# midi-switcher-smt.net
KiCad netlist of a schematic drawn in EAGLE
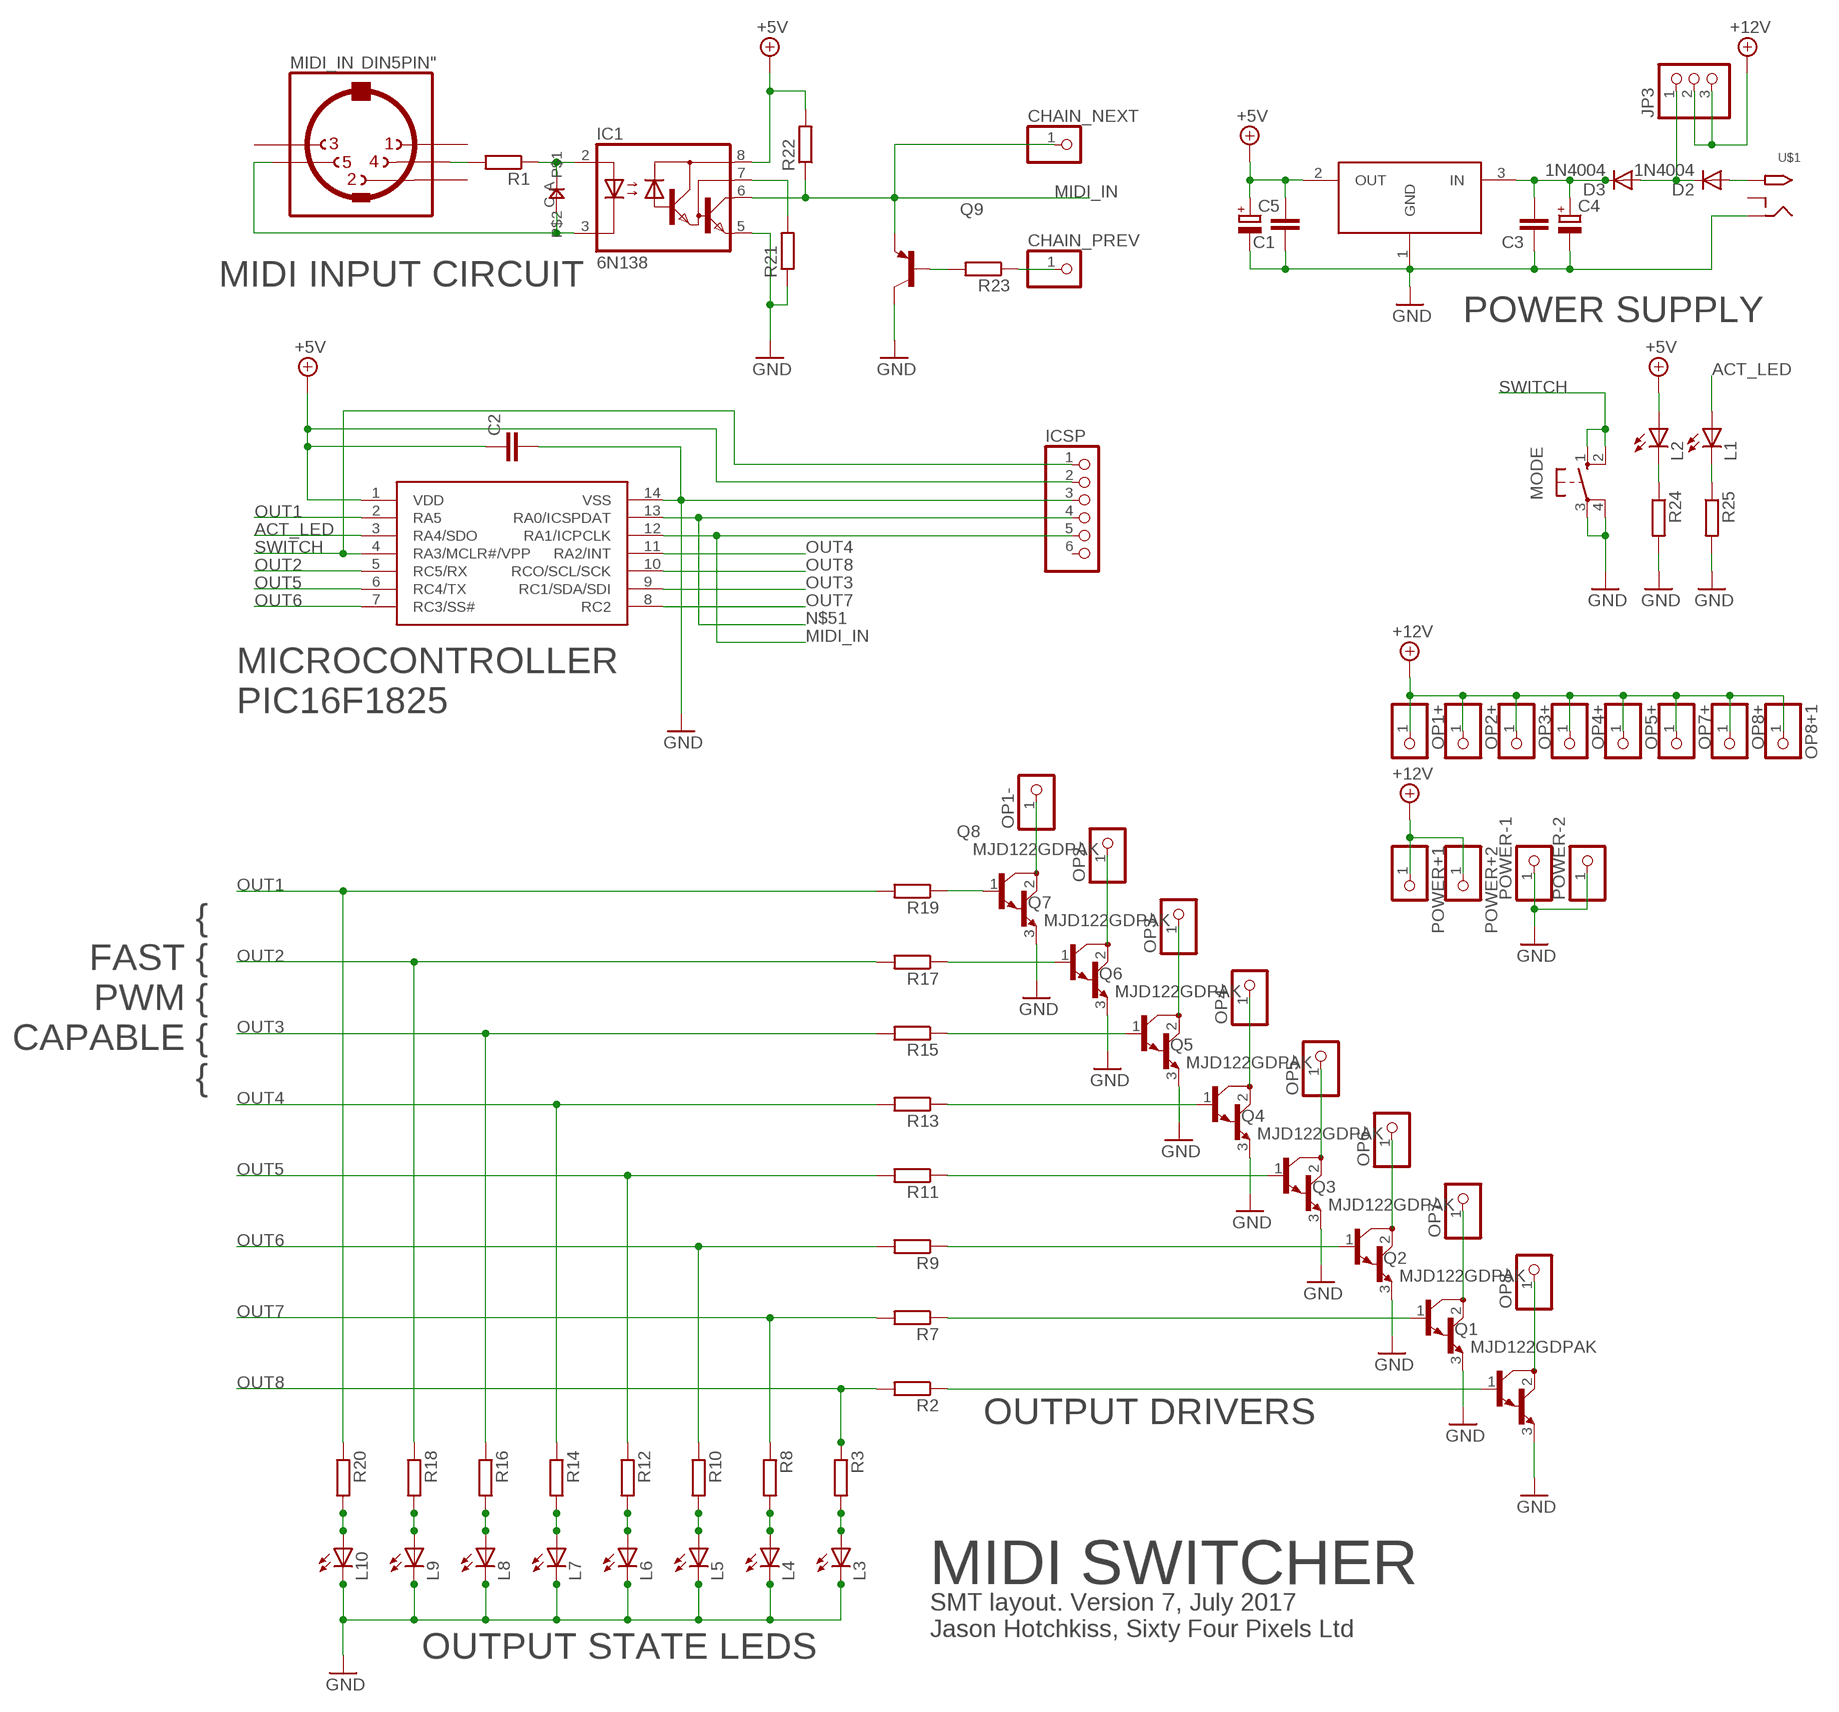
[diagram p0: schematic, sheet 1]

(export (version "E")
  (design (tool "Eeschema 10.0.6"))
  (components
    (comp (ref "C1")
      (value "C-EUC0805")
      (footprint "eagle-import:C0805")
      (libsource (lib "eagle-import") (part "C-EUC0805"))
    )
    (comp (ref "C2")
      (value "C-EUC0805")
      (footprint "eagle-import:C0805")
      (libsource (lib "eagle-import") (part "C-EUC0805"))
    )
    (comp (ref "C3")
      (value "C-EUC0805")
      (footprint "eagle-import:C0805")
      (libsource (lib "eagle-import") (part "C-EUC0805"))
    )
    (comp (ref "C4")
      (value "CPOL-EUE2.5-7")
      (footprint "eagle-import:E2,5-7")
      (libsource (lib "eagle-import") (part "CPOL-EUE2.5-7"))
    )
    (comp (ref "C5")
      (value "CPOL-EUE2.5-6")
      (footprint "eagle-import:E2,5-6")
      (libsource (lib "eagle-import") (part "CPOL-EUE2.5-6"))
    )
    (comp (ref "CHAIN_NEXT")
      (value "PINHD-1X1")
      (footprint "eagle-import:1X01")
      (libsource (lib "eagle-import") (part "PINHD-1X1"))
    )
    (comp (ref "CHAIN_PREV")
      (value "PINHD-1X1")
      (footprint "eagle-import:1X01")
      (libsource (lib "eagle-import") (part "PINHD-1X1"))
    )
    (comp (ref "D1")
      (value "0805DIODE")
      (footprint "eagle-import:0805DIODE")
      (libsource (lib "eagle-import") (part "0805DIODE"))
    )
    (comp (ref "D2")
      (value "1N4004")
      (footprint "eagle-import:DO-VERT")
      (libsource (lib "eagle-import") (part "1N4004"))
    )
    (comp (ref "D3")
      (value "1N4004")
      (footprint "eagle-import:DO-VERT")
      (libsource (lib "eagle-import") (part "1N4004"))
    )
    (comp (ref "IC1")
      (value "6N138")
      (footprint "eagle-import:DIL08")
      (libsource (lib "eagle-import") (part "6N138"))
    )
    (comp (ref "IC2")
      (value "PIC16F1825SO14")
      (footprint "eagle-import:SO14")
      (libsource (lib "eagle-import") (part "PIC16F1825SO14"))
    )
    (comp (ref "IC3")
      (value "LD1086")
      (footprint "eagle-import:DPACK")
      (libsource (lib "eagle-import") (part "LD1086"))
    )
    (comp (ref "ICSP")
      (value "HEADER-1X6")
      (footprint "eagle-import:1X06_OVAL")
      (libsource (lib "eagle-import") (part "HEADER-1X6"))
    )
    (comp (ref "JP3")
      (value "PINHD-1X3")
      (footprint "eagle-import:1X03")
      (libsource (lib "eagle-import") (part "PINHD-1X3"))
    )
    (comp (ref "L1")
      (value "LEDCHIP-LED0805")
      (footprint "eagle-import:CHIP-LED0805")
      (libsource (lib "eagle-import") (part "LEDCHIP-LED0805"))
    )
    (comp (ref "L2")
      (value "LEDCHIP-LED0805")
      (footprint "eagle-import:CHIP-LED0805")
      (libsource (lib "eagle-import") (part "LEDCHIP-LED0805"))
    )
    (comp (ref "L3")
      (value "LEDCHIP-LED0805")
      (footprint "eagle-import:CHIP-LED0805")
      (libsource (lib "eagle-import") (part "LEDCHIP-LED0805"))
    )
    (comp (ref "L4")
      (value "LEDCHIP-LED0805")
      (footprint "eagle-import:CHIP-LED0805")
      (libsource (lib "eagle-import") (part "LEDCHIP-LED0805"))
    )
    (comp (ref "L5")
      (value "LEDCHIP-LED0805")
      (footprint "eagle-import:CHIP-LED0805")
      (libsource (lib "eagle-import") (part "LEDCHIP-LED0805"))
    )
    (comp (ref "L6")
      (value "LEDCHIP-LED0805")
      (footprint "eagle-import:CHIP-LED0805")
      (libsource (lib "eagle-import") (part "LEDCHIP-LED0805"))
    )
    (comp (ref "L7")
      (value "LEDCHIP-LED0805")
      (footprint "eagle-import:CHIP-LED0805")
      (libsource (lib "eagle-import") (part "LEDCHIP-LED0805"))
    )
    (comp (ref "L8")
      (value "LEDCHIP-LED0805")
      (footprint "eagle-import:CHIP-LED0805")
      (libsource (lib "eagle-import") (part "LEDCHIP-LED0805"))
    )
    (comp (ref "L9")
      (value "LEDCHIP-LED0805")
      (footprint "eagle-import:CHIP-LED0805")
      (libsource (lib "eagle-import") (part "LEDCHIP-LED0805"))
    )
    (comp (ref "L10")
      (value "LEDCHIP-LED0805")
      (footprint "eagle-import:CHIP-LED0805")
      (libsource (lib "eagle-import") (part "LEDCHIP-LED0805"))
    )
    (comp (ref "MIDI_IN")
      (value "DIN5PIN\"")
      (footprint "eagle-import:TRUCONN90")
      (libsource (lib "eagle-import") (part "DIN5PIN{dblquote}"))
    )
    (comp (ref "MODE")
      (value "10-XX")
      (footprint "eagle-import:B3F-10XX")
      (libsource (lib "eagle-import") (part "10-XX"))
    )
    (comp (ref "OP1+")
      (value "PINHD-1X1")
      (footprint "eagle-import:1X01W")
      (libsource (lib "eagle-import") (part "jason_eagle6_PINHD-1X1"))
    )
    (comp (ref "OP1-")
      (value "PINHD-1X1")
      (footprint "eagle-import:1X01W")
      (libsource (lib "eagle-import") (part "jason_eagle6_PINHD-1X1"))
    )
    (comp (ref "OP2+")
      (value "PINHD-1X1")
      (footprint "eagle-import:1X01W")
      (libsource (lib "eagle-import") (part "jason_eagle6_PINHD-1X1"))
    )
    (comp (ref "OP2-")
      (value "PINHD-1X1")
      (footprint "eagle-import:1X01W")
      (libsource (lib "eagle-import") (part "jason_eagle6_PINHD-1X1"))
    )
    (comp (ref "OP3+")
      (value "PINHD-1X1")
      (footprint "eagle-import:1X01W")
      (libsource (lib "eagle-import") (part "jason_eagle6_PINHD-1X1"))
    )
    (comp (ref "OP3-")
      (value "PINHD-1X1")
      (footprint "eagle-import:1X01W")
      (libsource (lib "eagle-import") (part "jason_eagle6_PINHD-1X1"))
    )
    (comp (ref "OP4+")
      (value "PINHD-1X1")
      (footprint "eagle-import:1X01W")
      (libsource (lib "eagle-import") (part "jason_eagle6_PINHD-1X1"))
    )
    (comp (ref "OP4-")
      (value "PINHD-1X1")
      (footprint "eagle-import:1X01W")
      (libsource (lib "eagle-import") (part "jason_eagle6_PINHD-1X1"))
    )
    (comp (ref "OP5+")
      (value "PINHD-1X1")
      (footprint "eagle-import:1X01W")
      (libsource (lib "eagle-import") (part "jason_eagle6_PINHD-1X1"))
    )
    (comp (ref "OP5-")
      (value "PINHD-1X1")
      (footprint "eagle-import:1X01W")
      (libsource (lib "eagle-import") (part "jason_eagle6_PINHD-1X1"))
    )
    (comp (ref "OP6-")
      (value "PINHD-1X1")
      (footprint "eagle-import:1X01W")
      (libsource (lib "eagle-import") (part "jason_eagle6_PINHD-1X1"))
    )
    (comp (ref "OP7+")
      (value "PINHD-1X1")
      (footprint "eagle-import:1X01W")
      (libsource (lib "eagle-import") (part "jason_eagle6_PINHD-1X1"))
    )
    (comp (ref "OP7-")
      (value "PINHD-1X1")
      (footprint "eagle-import:1X01W")
      (libsource (lib "eagle-import") (part "jason_eagle6_PINHD-1X1"))
    )
    (comp (ref "OP8+")
      (value "PINHD-1X1")
      (footprint "eagle-import:1X01W")
      (libsource (lib "eagle-import") (part "jason_eagle6_PINHD-1X1"))
    )
    (comp (ref "OP8+1")
      (value "PINHD-1X1")
      (footprint "eagle-import:1X01W")
      (libsource (lib "eagle-import") (part "jason_eagle6_PINHD-1X1"))
    )
    (comp (ref "OP8-")
      (value "PINHD-1X1")
      (footprint "eagle-import:1X01W")
      (libsource (lib "eagle-import") (part "jason_eagle6_PINHD-1X1"))
    )
    (comp (ref "POWER+1")
      (value "PINHD-1X1")
      (footprint "eagle-import:1X01W")
      (libsource (lib "eagle-import") (part "jason_eagle6_PINHD-1X1"))
    )
    (comp (ref "POWER+2")
      (value "PINHD-1X1")
      (footprint "eagle-import:1X01W")
      (libsource (lib "eagle-import") (part "jason_eagle6_PINHD-1X1"))
    )
    (comp (ref "POWER-1")
      (value "PINHD-1X1")
      (footprint "eagle-import:1X01W")
      (libsource (lib "eagle-import") (part "jason_eagle6_PINHD-1X1"))
    )
    (comp (ref "POWER-2")
      (value "PINHD-1X1")
      (footprint "eagle-import:1X01W")
      (libsource (lib "eagle-import") (part "jason_eagle6_PINHD-1X1"))
    )
    (comp (ref "Q1")
      (value "MJD122GDPAK")
      (footprint "eagle-import:DPACK")
      (libsource (lib "eagle-import") (part "MJD122GDPAK"))
    )
    (comp (ref "Q2")
      (value "MJD122GDPAK")
      (footprint "eagle-import:DPACK")
      (libsource (lib "eagle-import") (part "MJD122GDPAK"))
    )
    (comp (ref "Q3")
      (value "MJD122GDPAK")
      (footprint "eagle-import:DPACK")
      (libsource (lib "eagle-import") (part "MJD122GDPAK"))
    )
    (comp (ref "Q4")
      (value "MJD122GDPAK")
      (footprint "eagle-import:DPACK")
      (libsource (lib "eagle-import") (part "MJD122GDPAK"))
    )
    (comp (ref "Q5")
      (value "MJD122GDPAK")
      (footprint "eagle-import:DPACK")
      (libsource (lib "eagle-import") (part "MJD122GDPAK"))
    )
    (comp (ref "Q6")
      (value "MJD122GDPAK")
      (footprint "eagle-import:DPACK")
      (libsource (lib "eagle-import") (part "MJD122GDPAK"))
    )
    (comp (ref "Q7")
      (value "MJD122GDPAK")
      (footprint "eagle-import:DPACK")
      (libsource (lib "eagle-import") (part "MJD122GDPAK"))
    )
    (comp (ref "Q8")
      (value "MJD122GDPAK")
      (footprint "eagle-import:DPACK")
      (libsource (lib "eagle-import") (part "MJD122GDPAK"))
    )
    (comp (ref "Q9")
      (value "MMBT3906LT1-PNP-SOT23-BEC")
      (footprint "eagle-import:SOT23-BEC")
      (libsource (lib "eagle-import") (part "-PNP-SOT23-BECMMBT3906LT1"))
    )
    (comp (ref "R1")
      (value "R-EU_R0805")
      (footprint "eagle-import:R0805")
      (libsource (lib "eagle-import") (part "R-EU_R0805"))
    )
    (comp (ref "R2")
      (value "R-EU_R0805")
      (footprint "eagle-import:R0805")
      (libsource (lib "eagle-import") (part "R-EU_R0805"))
    )
    (comp (ref "R3")
      (value "R-EU_R0805")
      (footprint "eagle-import:R0805")
      (libsource (lib "eagle-import") (part "R-EU_R0805"))
    )
    (comp (ref "R7")
      (value "R-EU_R0805")
      (footprint "eagle-import:R0805")
      (libsource (lib "eagle-import") (part "R-EU_R0805"))
    )
    (comp (ref "R8")
      (value "R-EU_R0805")
      (footprint "eagle-import:R0805")
      (libsource (lib "eagle-import") (part "R-EU_R0805"))
    )
    (comp (ref "R9")
      (value "R-EU_R0805")
      (footprint "eagle-import:R0805")
      (libsource (lib "eagle-import") (part "R-EU_R0805"))
    )
    (comp (ref "R10")
      (value "R-EU_R0805")
      (footprint "eagle-import:R0805")
      (libsource (lib "eagle-import") (part "R-EU_R0805"))
    )
    (comp (ref "R11")
      (value "R-EU_R0805")
      (footprint "eagle-import:R0805")
      (libsource (lib "eagle-import") (part "R-EU_R0805"))
    )
    (comp (ref "R12")
      (value "R-EU_R0805")
      (footprint "eagle-import:R0805")
      (libsource (lib "eagle-import") (part "R-EU_R0805"))
    )
    (comp (ref "R13")
      (value "R-EU_R0805")
      (footprint "eagle-import:R0805")
      (libsource (lib "eagle-import") (part "R-EU_R0805"))
    )
    (comp (ref "R14")
      (value "R-EU_R0805")
      (footprint "eagle-import:R0805")
      (libsource (lib "eagle-import") (part "R-EU_R0805"))
    )
    (comp (ref "R15")
      (value "R-EU_R0805")
      (footprint "eagle-import:R0805")
      (libsource (lib "eagle-import") (part "R-EU_R0805"))
    )
    (comp (ref "R16")
      (value "R-EU_R0805")
      (footprint "eagle-import:R0805")
      (libsource (lib "eagle-import") (part "R-EU_R0805"))
    )
    (comp (ref "R17")
      (value "R-EU_R0805")
      (footprint "eagle-import:R0805")
      (libsource (lib "eagle-import") (part "R-EU_R0805"))
    )
    (comp (ref "R18")
      (value "R-EU_R0805")
      (footprint "eagle-import:R0805")
      (libsource (lib "eagle-import") (part "R-EU_R0805"))
    )
    (comp (ref "R19")
      (value "R-EU_R0805")
      (footprint "eagle-import:R0805")
      (libsource (lib "eagle-import") (part "R-EU_R0805"))
    )
    (comp (ref "R20")
      (value "R-EU_R0805")
      (footprint "eagle-import:R0805")
      (libsource (lib "eagle-import") (part "R-EU_R0805"))
    )
    (comp (ref "R21")
      (value "R-EU_R0805")
      (footprint "eagle-import:R0805")
      (libsource (lib "eagle-import") (part "R-EU_R0805"))
    )
    (comp (ref "R22")
      (value "R-EU_R0805")
      (footprint "eagle-import:R0805")
      (libsource (lib "eagle-import") (part "R-EU_R0805"))
    )
    (comp (ref "R23")
      (value "R-EU_R0805")
      (footprint "eagle-import:R0805")
      (libsource (lib "eagle-import") (part "R-EU_R0805"))
    )
    (comp (ref "R24")
      (value "R-EU_R0805")
      (footprint "eagle-import:R0805")
      (libsource (lib "eagle-import") (part "R-EU_R0805"))
    )
    (comp (ref "R25")
      (value "R-EU_R0805")
      (footprint "eagle-import:R0805")
      (libsource (lib "eagle-import") (part "R-EU_R0805"))
    )
    (comp (ref "U$1")
      (value "2.1MMJACKTHM")
      (footprint "eagle-import:PJ-102A")
      (libsource (lib "eagle-import") (part "2.1MMJACKTHM"))
    )
  )
  (nets
    (net (code "1") (name "+5V") (class "Default")
      (node (ref "C1") (pin "2") (pinfunction "2_2") (pintype "passive"))
      (node (ref "C2") (pin "1") (pinfunction "1_1") (pintype "passive"))
      (node (ref "C5") (pin "+") (pinfunction "+_+") (pintype "passive"))
      (node (ref "IC1") (pin "8") (pinfunction "VCC_8") (pintype "passive"))
      (node (ref "IC2") (pin "1") (pinfunction "VDD_1") (pintype "power_in"))
      (node (ref "IC3") (pin "2") (pinfunction "OUT_2") (pintype "bidirectional"))
      (node (ref "ICSP") (pin "2") (pinfunction "2_2") (pintype "passive"))
      (node (ref "L2") (pin "A") (pinfunction "A_A") (pintype "passive"))
      (node (ref "R22") (pin "2") (pinfunction "2_2") (pintype "passive"))
    )
    (net (code "2") (name "+12V") (class "Default")
      (node (ref "JP3") (pin "2") (pinfunction "2_2") (pintype "passive"))
      (node (ref "JP3") (pin "3") (pinfunction "3_3") (pintype "passive"))
      (node (ref "OP1+") (pin "1") (pinfunction "1_1") (pintype "passive"))
      (node (ref "OP2+") (pin "1") (pinfunction "1_1") (pintype "passive"))
      (node (ref "OP3+") (pin "1") (pinfunction "1_1") (pintype "passive"))
      (node (ref "OP4+") (pin "1") (pinfunction "1_1") (pintype "passive"))
      (node (ref "OP5+") (pin "1") (pinfunction "1_1") (pintype "passive"))
      (node (ref "OP7+") (pin "1") (pinfunction "1_1") (pintype "passive"))
      (node (ref "OP8+") (pin "1") (pinfunction "1_1") (pintype "passive"))
      (node (ref "OP8+1") (pin "1") (pinfunction "1_1") (pintype "passive"))
      (node (ref "POWER+1") (pin "1") (pinfunction "1_1") (pintype "passive"))
      (node (ref "POWER+2") (pin "1") (pinfunction "1_1") (pintype "passive"))
    )
    (net (code "3") (name "/ACT_LED") (class "Default")
      (node (ref "IC2") (pin "3") (pinfunction "RA4/SDO_3") (pintype "bidirectional"))
      (node (ref "L1") (pin "A") (pinfunction "A_A") (pintype "passive"))
    )
    (net (code "4") (name "/MIDI_IN") (class "Default")
      (node (ref "CHAIN_NEXT") (pin "1") (pinfunction "1_1") (pintype "passive"))
      (node (ref "IC1") (pin "6") (pinfunction "VO_6") (pintype "passive"))
      (node (ref "IC2") (pin "12") (pinfunction "RA1/ICPCLK_12") (pintype "bidirectional"))
      (node (ref "ICSP") (pin "5") (pinfunction "5_5") (pintype "passive"))
      (node (ref "Q9") (pin "E") (pinfunction "E_E") (pintype "passive"))
      (node (ref "R22") (pin "1") (pinfunction "1_1") (pintype "passive"))
    )
    (net (code "5") (name "/N$51") (class "Default")
      (node (ref "IC2") (pin "13") (pinfunction "RA0/ICSPDAT_13") (pintype "bidirectional"))
      (node (ref "ICSP") (pin "4") (pinfunction "4_4") (pintype "passive"))
    )
    (net (code "6") (name "/OUT1") (class "Default")
      (node (ref "IC2") (pin "2") (pinfunction "RA5_2") (pintype "bidirectional"))
      (node (ref "R19") (pin "2") (pinfunction "2_2") (pintype "passive"))
      (node (ref "R20") (pin "1") (pinfunction "1_1") (pintype "passive"))
    )
    (net (code "7") (name "/OUT2") (class "Default")
      (node (ref "IC2") (pin "5") (pinfunction "RC5/RX_5") (pintype "bidirectional"))
      (node (ref "R17") (pin "2") (pinfunction "2_2") (pintype "passive"))
      (node (ref "R18") (pin "1") (pinfunction "1_1") (pintype "passive"))
    )
    (net (code "8") (name "/OUT3") (class "Default")
      (node (ref "IC2") (pin "9") (pinfunction "RC1/SDA/SDI_9") (pintype "bidirectional"))
      (node (ref "R15") (pin "2") (pinfunction "2_2") (pintype "passive"))
      (node (ref "R16") (pin "1") (pinfunction "1_1") (pintype "passive"))
    )
    (net (code "9") (name "/OUT4") (class "Default")
      (node (ref "IC2") (pin "11") (pinfunction "RA2/INT_11") (pintype "bidirectional"))
      (node (ref "R13") (pin "2") (pinfunction "2_2") (pintype "passive"))
      (node (ref "R14") (pin "1") (pinfunction "1_1") (pintype "passive"))
    )
    (net (code "10") (name "/OUT5") (class "Default")
      (node (ref "IC2") (pin "6") (pinfunction "RC4/TX_6") (pintype "bidirectional"))
      (node (ref "R11") (pin "2") (pinfunction "2_2") (pintype "passive"))
      (node (ref "R12") (pin "1") (pinfunction "1_1") (pintype "passive"))
    )
    (net (code "11") (name "/OUT6") (class "Default")
      (node (ref "IC2") (pin "7") (pinfunction "RC3/SS#_7") (pintype "bidirectional"))
      (node (ref "R10") (pin "1") (pinfunction "1_1") (pintype "passive"))
      (node (ref "R9") (pin "2") (pinfunction "2_2") (pintype "passive"))
    )
    (net (code "12") (name "/OUT7") (class "Default")
      (node (ref "IC2") (pin "8") (pinfunction "RC2_8") (pintype "bidirectional"))
      (node (ref "R7") (pin "2") (pinfunction "2_2") (pintype "passive"))
      (node (ref "R8") (pin "1") (pinfunction "1_1") (pintype "passive"))
    )
    (net (code "13") (name "/OUT8") (class "Default")
      (node (ref "IC2") (pin "10") (pinfunction "RCO/SCL/SCK_10") (pintype "bidirectional"))
      (node (ref "R2") (pin "2") (pinfunction "2_2") (pintype "passive"))
      (node (ref "R3") (pin "1") (pinfunction "1_1") (pintype "passive"))
    )
    (net (code "14") (name "/SWITCH") (class "Default")
      (node (ref "IC2") (pin "4") (pinfunction "RA3/MCLR#/VPP_4") (pintype "input"))
      (node (ref "ICSP") (pin "1") (pinfunction "1_1") (pintype "passive"))
      (node (ref "MODE") (pin "1") (pinfunction "S_1") (pintype "passive"))
      (node (ref "MODE") (pin "2") (pinfunction "S1_2") (pintype "passive"))
    )
    (net (code "15") (name "GND") (class "Default")
      (node (ref "C1") (pin "1") (pinfunction "1_1") (pintype "passive"))
      (node (ref "C2") (pin "2") (pinfunction "2_2") (pintype "passive"))
      (node (ref "C3") (pin "1") (pinfunction "1_1") (pintype "passive"))
      (node (ref "C4") (pin "-") (pinfunction "-_-") (pintype "passive"))
      (node (ref "C5") (pin "-") (pinfunction "-_-") (pintype "passive"))
      (node (ref "IC1") (pin "5") (pinfunction "GND_5") (pintype "passive"))
      (node (ref "IC2") (pin "14") (pinfunction "VSS_14") (pintype "power_in"))
      (node (ref "IC3") (pin "1") (pinfunction "GND_1") (pintype "bidirectional"))
      (node (ref "ICSP") (pin "3") (pinfunction "3_3") (pintype "passive"))
      (node (ref "L10") (pin "C") (pinfunction "C_C") (pintype "passive"))
      (node (ref "L3") (pin "C") (pinfunction "C_C") (pintype "passive"))
      (node (ref "L4") (pin "C") (pinfunction "C_C") (pintype "passive"))
      (node (ref "L5") (pin "C") (pinfunction "C_C") (pintype "passive"))
      (node (ref "L6") (pin "C") (pinfunction "C_C") (pintype "passive"))
      (node (ref "L7") (pin "C") (pinfunction "C_C") (pintype "passive"))
      (node (ref "L8") (pin "C") (pinfunction "C_C") (pintype "passive"))
      (node (ref "L9") (pin "C") (pinfunction "C_C") (pintype "passive"))
      (node (ref "MODE") (pin "3") (pinfunction "P_3") (pintype "passive"))
      (node (ref "MODE") (pin "4") (pinfunction "P1_4") (pintype "passive"))
      (node (ref "POWER-1") (pin "1") (pinfunction "1_1") (pintype "passive"))
      (node (ref "POWER-2") (pin "1") (pinfunction "1_1") (pintype "passive"))
      (node (ref "Q1") (pin "3") (pinfunction "E_3") (pintype "passive"))
      (node (ref "Q2") (pin "3") (pinfunction "E_3") (pintype "passive"))
      (node (ref "Q3") (pin "3") (pinfunction "E_3") (pintype "passive"))
      (node (ref "Q4") (pin "3") (pinfunction "E_3") (pintype "passive"))
      (node (ref "Q5") (pin "3") (pinfunction "E_3") (pintype "passive"))
      (node (ref "Q6") (pin "3") (pinfunction "E_3") (pintype "passive"))
      (node (ref "Q7") (pin "3") (pinfunction "E_3") (pintype "passive"))
      (node (ref "Q8") (pin "3") (pinfunction "E_3") (pintype "passive"))
      (node (ref "Q9") (pin "C") (pinfunction "C_C") (pintype "passive"))
      (node (ref "R21") (pin "1") (pinfunction "1_1") (pintype "passive"))
      (node (ref "R24") (pin "2") (pinfunction "2_2") (pintype "passive"))
      (node (ref "R25") (pin "2") (pinfunction "2_2") (pintype "passive"))
      (node (ref "U$1") (pin "RING") (pinfunction "RING_RING") (pintype "bidirectional"))
    )
    (net (code "16") (name "Net-(CHAIN_PREV-Pad1)") (class "Default")
      (node (ref "CHAIN_PREV") (pin "1") (pinfunction "1_1") (pintype "passive"))
      (node (ref "R23") (pin "1") (pinfunction "1_1") (pintype "passive"))
    )
    (net (code "17") (name "Net-(D1-P$1)") (class "Default")
      (node (ref "D1") (pin "C") (pinfunction "P$1_C") (pintype "bidirectional"))
      (node (ref "IC1") (pin "3") (pinfunction "C_3") (pintype "passive"))
      (node (ref "MIDI_IN") (pin "5") (pinfunction "5_5") (pintype "passive"))
    )
    (net (code "18") (name "Net-(D1-P$2)") (class "Default")
      (node (ref "D1") (pin "A") (pinfunction "P$2_A") (pintype "bidirectional"))
      (node (ref "IC1") (pin "2") (pinfunction "A_2") (pintype "passive"))
      (node (ref "R1") (pin "1") (pinfunction "1_1") (pintype "passive"))
    )
    (net (code "19") (name "Net-(D2-PadA)") (class "Default")
      (node (ref "D2") (pin "A") (pinfunction "A_A") (pintype "passive"))
      (node (ref "U$1") (pin "TIP") (pinfunction "TIP_TIP") (pintype "bidirectional"))
    )
    (net (code "20") (name "Net-(D2-PadC)") (class "Default")
      (node (ref "D2") (pin "C") (pinfunction "C_C") (pintype "passive"))
      (node (ref "D3") (pin "A") (pinfunction "A_A") (pintype "passive"))
      (node (ref "JP3") (pin "1") (pinfunction "1_1") (pintype "passive"))
    )
    (net (code "21") (name "Net-(IC1-VB)") (class "Default")
      (node (ref "IC1") (pin "7") (pinfunction "VB_7") (pintype "passive"))
      (node (ref "R21") (pin "2") (pinfunction "2_2") (pintype "passive"))
    )
    (net (code "22") (name "Net-(IC3-IN)") (class "Default")
      (node (ref "C3") (pin "2") (pinfunction "2_2") (pintype "passive"))
      (node (ref "C4") (pin "+") (pinfunction "+_+") (pintype "passive"))
      (node (ref "D3") (pin "C") (pinfunction "C_C") (pintype "passive"))
      (node (ref "IC3") (pin "3") (pinfunction "IN_3") (pintype "bidirectional"))
    )
    (net (code "23") (name "Net-(L1-PadC)") (class "Default")
      (node (ref "L1") (pin "C") (pinfunction "C_C") (pintype "passive"))
      (node (ref "R25") (pin "1") (pinfunction "1_1") (pintype "passive"))
    )
    (net (code "24") (name "Net-(L2-PadC)") (class "Default")
      (node (ref "L2") (pin "C") (pinfunction "C_C") (pintype "passive"))
      (node (ref "R24") (pin "1") (pinfunction "1_1") (pintype "passive"))
    )
    (net (code "25") (name "Net-(L3-PadA)") (class "Default")
      (node (ref "L3") (pin "A") (pinfunction "A_A") (pintype "passive"))
      (node (ref "R3") (pin "2") (pinfunction "2_2") (pintype "passive"))
    )
    (net (code "26") (name "Net-(L4-PadA)") (class "Default")
      (node (ref "L4") (pin "A") (pinfunction "A_A") (pintype "passive"))
      (node (ref "R8") (pin "2") (pinfunction "2_2") (pintype "passive"))
    )
    (net (code "27") (name "Net-(L5-PadA)") (class "Default")
      (node (ref "L5") (pin "A") (pinfunction "A_A") (pintype "passive"))
      (node (ref "R10") (pin "2") (pinfunction "2_2") (pintype "passive"))
    )
    (net (code "28") (name "Net-(L6-PadA)") (class "Default")
      (node (ref "L6") (pin "A") (pinfunction "A_A") (pintype "passive"))
      (node (ref "R12") (pin "2") (pinfunction "2_2") (pintype "passive"))
    )
    (net (code "29") (name "Net-(L7-PadA)") (class "Default")
      (node (ref "L7") (pin "A") (pinfunction "A_A") (pintype "passive"))
      (node (ref "R14") (pin "2") (pinfunction "2_2") (pintype "passive"))
    )
    (net (code "30") (name "Net-(L8-PadA)") (class "Default")
      (node (ref "L8") (pin "A") (pinfunction "A_A") (pintype "passive"))
      (node (ref "R16") (pin "2") (pinfunction "2_2") (pintype "passive"))
    )
    (net (code "31") (name "Net-(L9-PadA)") (class "Default")
      (node (ref "L9") (pin "A") (pinfunction "A_A") (pintype "passive"))
      (node (ref "R18") (pin "2") (pinfunction "2_2") (pintype "passive"))
    )
    (net (code "32") (name "Net-(L10-PadA)") (class "Default")
      (node (ref "L10") (pin "A") (pinfunction "A_A") (pintype "passive"))
      (node (ref "R20") (pin "2") (pinfunction "2_2") (pintype "passive"))
    )
    (net (code "33") (name "Net-(MIDI_IN-Pad4)") (class "Default")
      (node (ref "MIDI_IN") (pin "4") (pinfunction "4_4") (pintype "passive"))
      (node (ref "R1") (pin "2") (pinfunction "2_2") (pintype "passive"))
    )
    (net (code "34") (name "Net-(Q1-B)") (class "Default")
      (node (ref "Q1") (pin "1") (pinfunction "B_1") (pintype "passive"))
      (node (ref "R2") (pin "1") (pinfunction "1_1") (pintype "passive"))
    )
    (net (code "35") (name "Net-(Q1-C)") (class "Default")
      (node (ref "OP8-") (pin "1") (pinfunction "1_1") (pintype "passive"))
      (node (ref "Q1") (pin "2") (pinfunction "C_2") (pintype "passive"))
    )
    (net (code "36") (name "Net-(Q2-B)") (class "Default")
      (node (ref "Q2") (pin "1") (pinfunction "B_1") (pintype "passive"))
      (node (ref "R7") (pin "1") (pinfunction "1_1") (pintype "passive"))
    )
    (net (code "37") (name "Net-(Q2-C)") (class "Default")
      (node (ref "OP7-") (pin "1") (pinfunction "1_1") (pintype "passive"))
      (node (ref "Q2") (pin "2") (pinfunction "C_2") (pintype "passive"))
    )
    (net (code "38") (name "Net-(Q3-B)") (class "Default")
      (node (ref "Q3") (pin "1") (pinfunction "B_1") (pintype "passive"))
      (node (ref "R9") (pin "1") (pinfunction "1_1") (pintype "passive"))
    )
    (net (code "39") (name "Net-(Q3-C)") (class "Default")
      (node (ref "OP6-") (pin "1") (pinfunction "1_1") (pintype "passive"))
      (node (ref "Q3") (pin "2") (pinfunction "C_2") (pintype "passive"))
    )
    (net (code "40") (name "Net-(Q4-B)") (class "Default")
      (node (ref "Q4") (pin "1") (pinfunction "B_1") (pintype "passive"))
      (node (ref "R11") (pin "1") (pinfunction "1_1") (pintype "passive"))
    )
    (net (code "41") (name "Net-(Q4-C)") (class "Default")
      (node (ref "OP5-") (pin "1") (pinfunction "1_1") (pintype "passive"))
      (node (ref "Q4") (pin "2") (pinfunction "C_2") (pintype "passive"))
    )
    (net (code "42") (name "Net-(Q5-B)") (class "Default")
      (node (ref "Q5") (pin "1") (pinfunction "B_1") (pintype "passive"))
      (node (ref "R13") (pin "1") (pinfunction "1_1") (pintype "passive"))
    )
    (net (code "43") (name "Net-(Q5-C)") (class "Default")
      (node (ref "OP4-") (pin "1") (pinfunction "1_1") (pintype "passive"))
      (node (ref "Q5") (pin "2") (pinfunction "C_2") (pintype "passive"))
    )
    (net (code "44") (name "Net-(Q6-B)") (class "Default")
      (node (ref "Q6") (pin "1") (pinfunction "B_1") (pintype "passive"))
      (node (ref "R15") (pin "1") (pinfunction "1_1") (pintype "passive"))
    )
    (net (code "45") (name "Net-(Q6-C)") (class "Default")
      (node (ref "OP3-") (pin "1") (pinfunction "1_1") (pintype "passive"))
      (node (ref "Q6") (pin "2") (pinfunction "C_2") (pintype "passive"))
    )
    (net (code "46") (name "Net-(Q7-B)") (class "Default")
      (node (ref "Q7") (pin "1") (pinfunction "B_1") (pintype "passive"))
      (node (ref "R17") (pin "1") (pinfunction "1_1") (pintype "passive"))
    )
    (net (code "47") (name "Net-(Q7-C)") (class "Default")
      (node (ref "OP2-") (pin "1") (pinfunction "1_1") (pintype "passive"))
      (node (ref "Q7") (pin "2") (pinfunction "C_2") (pintype "passive"))
    )
    (net (code "48") (name "Net-(Q8-B)") (class "Default")
      (node (ref "Q8") (pin "1") (pinfunction "B_1") (pintype "passive"))
      (node (ref "R19") (pin "1") (pinfunction "1_1") (pintype "passive"))
    )
    (net (code "49") (name "Net-(Q8-C)") (class "Default")
      (node (ref "OP1-") (pin "1") (pinfunction "1_1") (pintype "passive"))
      (node (ref "Q8") (pin "2") (pinfunction "C_2") (pintype "passive"))
    )
    (net (code "50") (name "Net-(Q9-PadB)") (class "Default")
      (node (ref "Q9") (pin "B") (pinfunction "B_B") (pintype "passive"))
      (node (ref "R23") (pin "2") (pinfunction "2_2") (pintype "passive"))
    )
    (net (code "51") (name "unconnected-(ICSP-Pad6)") (class "Default")
      (node (ref "ICSP") (pin "6") (pinfunction "6_6") (pintype "passive"))
    )
    (net (code "52") (name "unconnected-(MIDI_IN-Pad1)") (class "Default")
      (node (ref "MIDI_IN") (pin "1") (pinfunction "1_1") (pintype "passive"))
    )
    (net (code "53") (name "unconnected-(MIDI_IN-Pad2)") (class "Default")
      (node (ref "MIDI_IN") (pin "2") (pinfunction "2_2") (pintype "passive"))
    )
    (net (code "54") (name "unconnected-(MIDI_IN-Pad3)") (class "Default")
      (node (ref "MIDI_IN") (pin "3") (pinfunction "3_3") (pintype "passive"))
    )
    (net (code "55") (name "unconnected-(U$1-PadRING_SW)") (class "Default")
      (node (ref "U$1") (pin "RING_SW") (pinfunction "RING_SW_RING_SW") (pintype "bidirectional"))
    )
  )
)
